# Swarm_Board_3.net
KiCad netlist of a schematic drawn in EAGLE
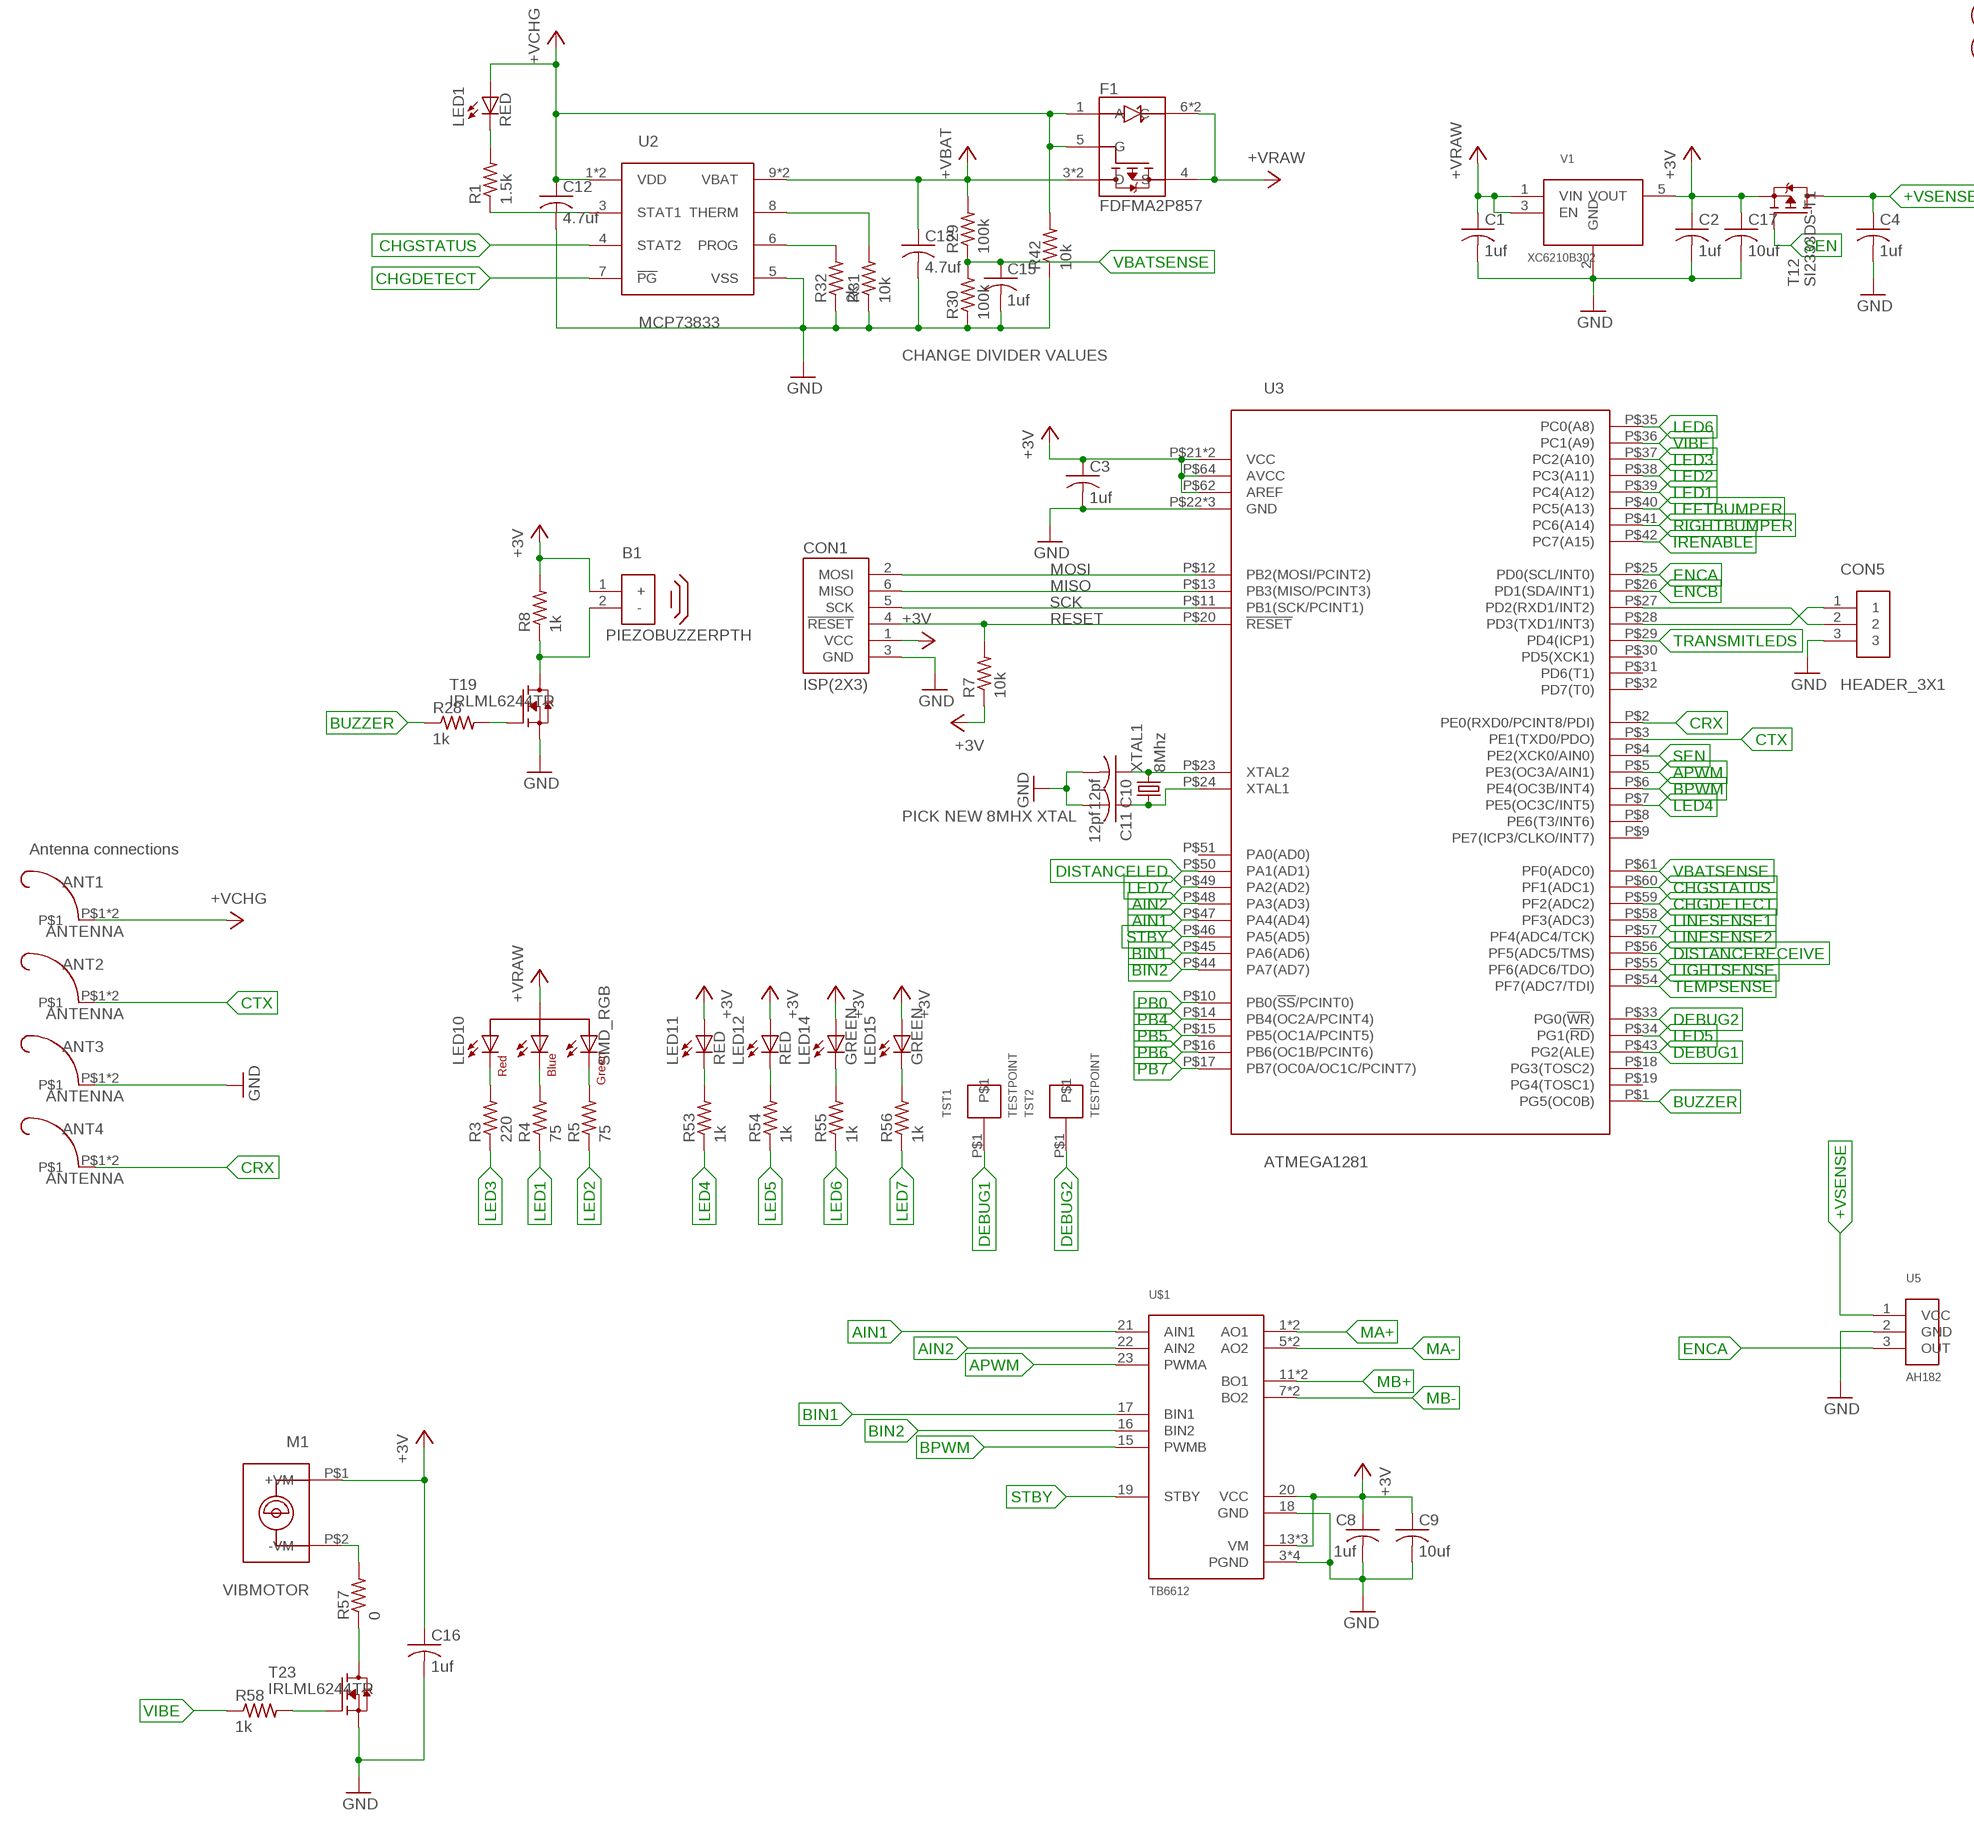
[diagram p0: schematic, sheet 1, part 1 of 2]
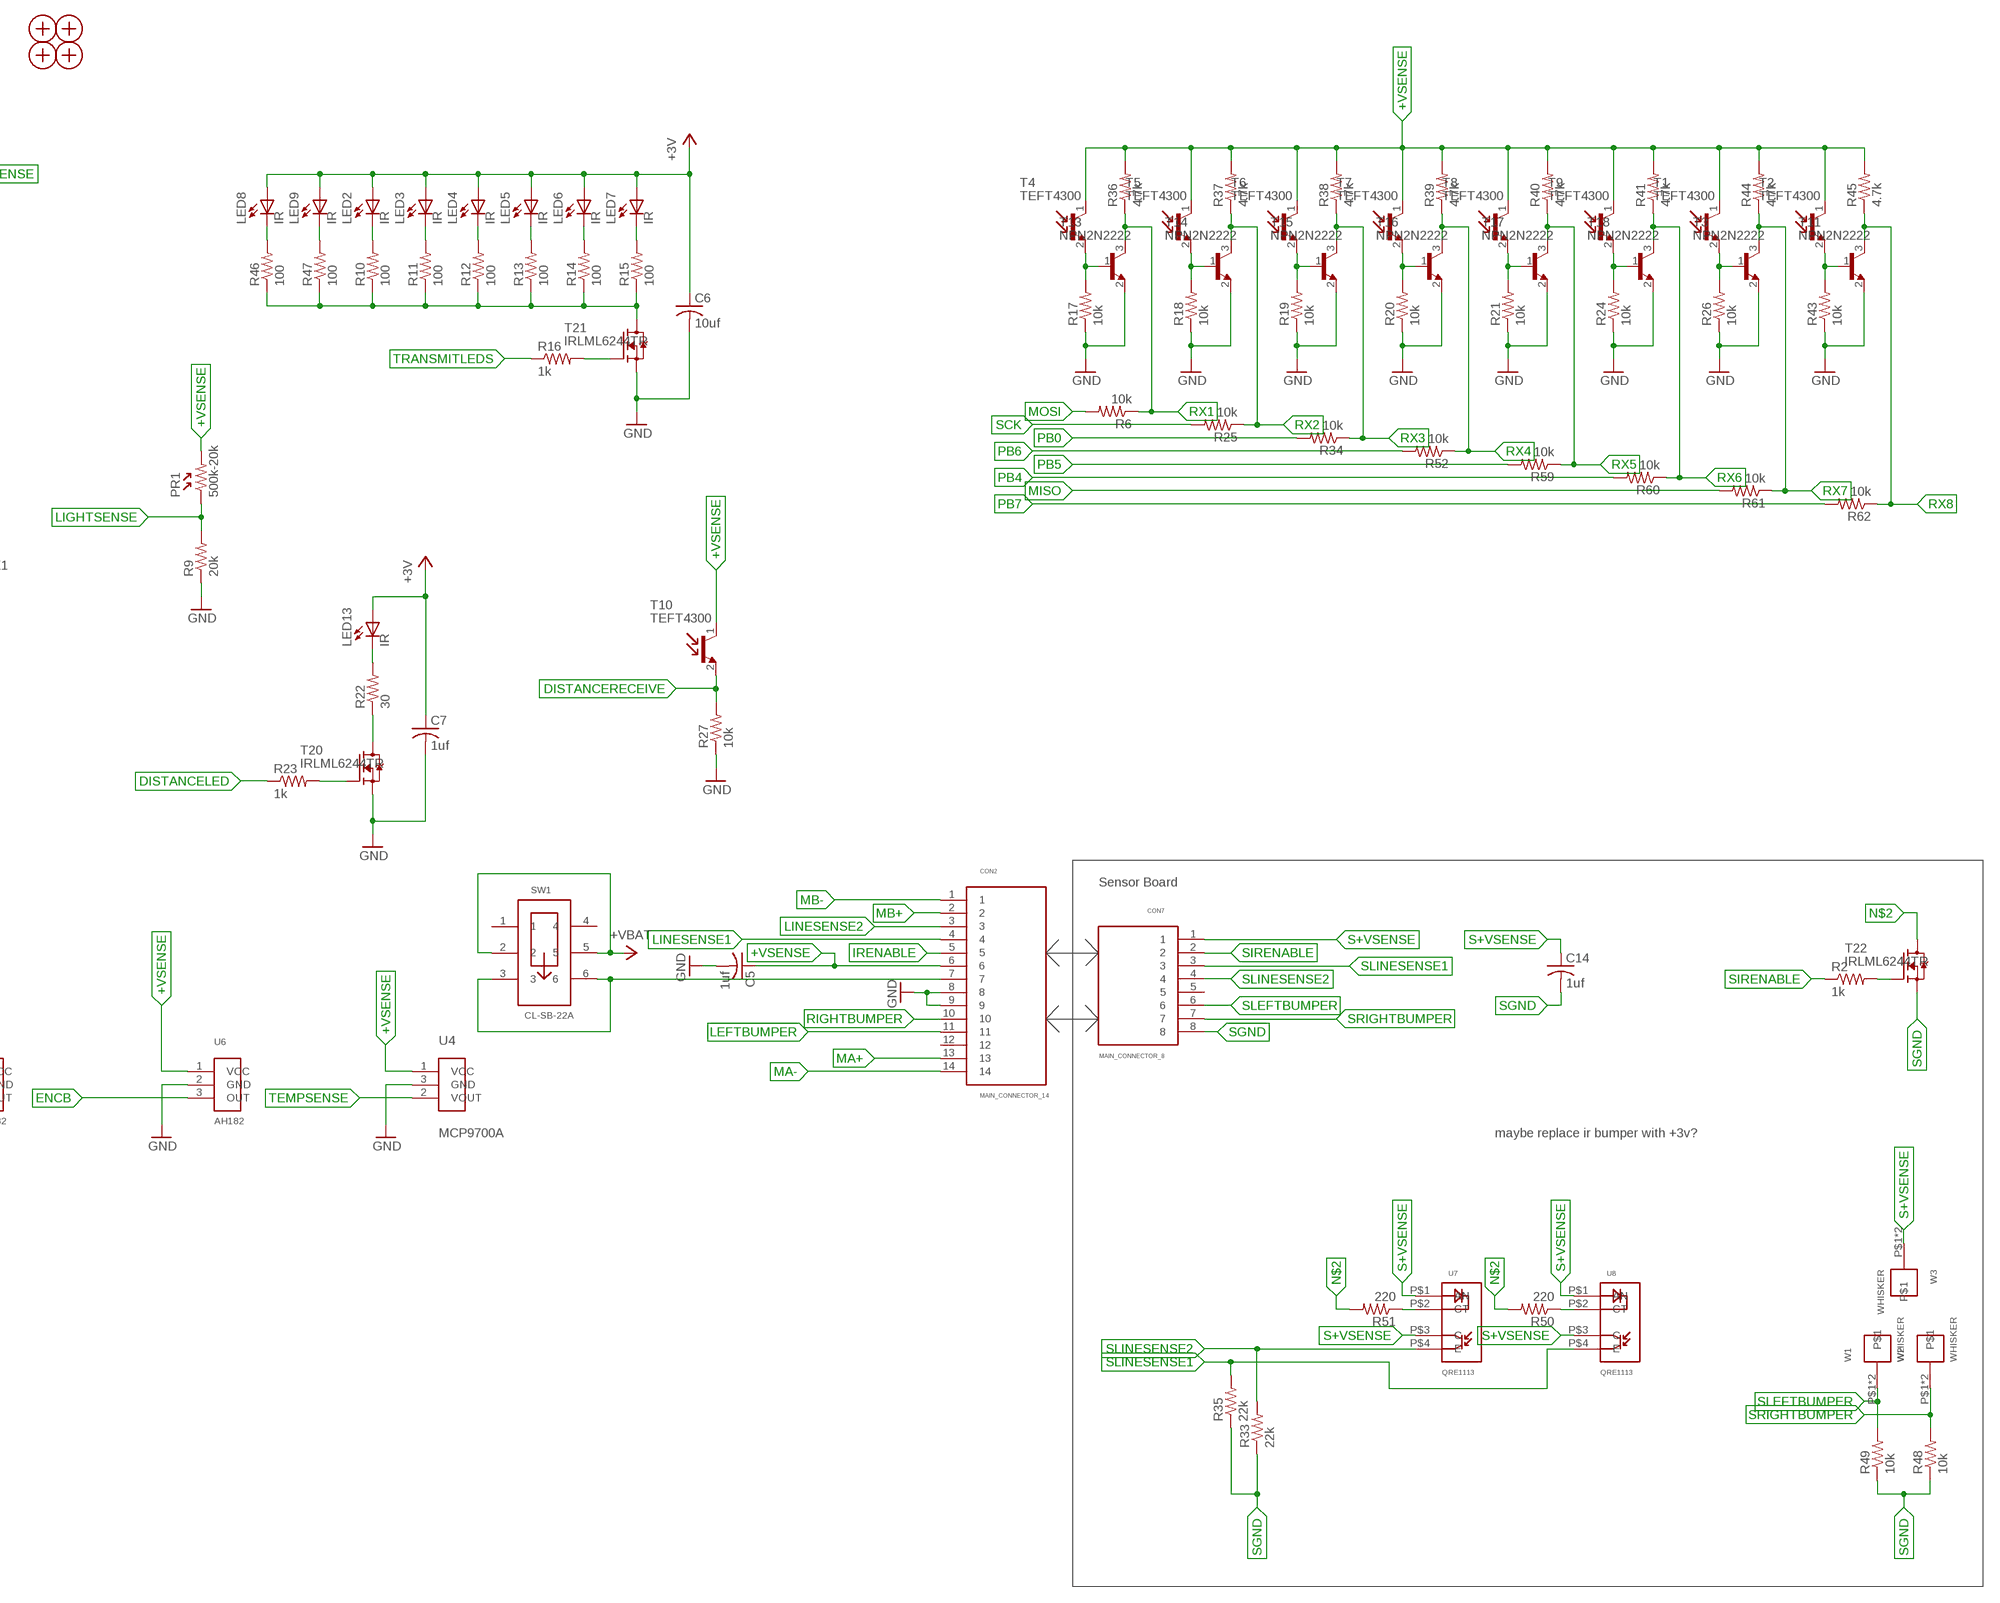
[diagram p1: schematic, sheet 1, part 2 of 2]

(export (version "E")
  (design (tool "Eeschema 10.0.6"))
  (components
    (comp (ref "ANT1")
      (value "ANTENNA")
      (footprint "eagle-import:ANTENNA")
      (libsource (lib "eagle-import") (part "ANTENNA"))
    )
    (comp (ref "ANT2")
      (value "ANTENNA")
      (footprint "eagle-import:ANTENNA")
      (libsource (lib "eagle-import") (part "ANTENNA"))
    )
    (comp (ref "ANT3")
      (value "ANTENNA")
      (footprint "eagle-import:ANTENNA")
      (libsource (lib "eagle-import") (part "ANTENNA"))
    )
    (comp (ref "ANT4")
      (value "ANTENNA")
      (footprint "eagle-import:ANTENNA")
      (libsource (lib "eagle-import") (part "ANTENNA"))
    )
    (comp (ref "B1")
      (value "PIEZOBUZZERPTH")
      (footprint "eagle-import:PIEZOBUZZER")
      (libsource (lib "eagle-import") (part "PIEZOBUZZERPTH"))
    )
    (comp (ref "C1")
      (value "1uf")
      (footprint "eagle-import:0603")
      (libsource (lib "eagle-import") (part "CAP0603"))
    )
    (comp (ref "C2")
      (value "1uf")
      (footprint "eagle-import:0603")
      (libsource (lib "eagle-import") (part "CAP0603"))
    )
    (comp (ref "C3")
      (value "1uf")
      (footprint "eagle-import:0603")
      (libsource (lib "eagle-import") (part "CAP0603"))
    )
    (comp (ref "C4")
      (value "1uf")
      (footprint "eagle-import:0603")
      (libsource (lib "eagle-import") (part "CAP0603"))
    )
    (comp (ref "C5")
      (value "1uf")
      (footprint "eagle-import:0603")
      (libsource (lib "eagle-import") (part "CAP0603"))
    )
    (comp (ref "C6")
      (value "10uf")
      (footprint "eagle-import:0805")
      (libsource (lib "eagle-import") (part "CAP0805"))
    )
    (comp (ref "C7")
      (value "1uf")
      (footprint "eagle-import:0603")
      (libsource (lib "eagle-import") (part "CAP0603"))
    )
    (comp (ref "C8")
      (value "1uf")
      (footprint "eagle-import:0603")
      (libsource (lib "eagle-import") (part "CAP0603"))
    )
    (comp (ref "C9")
      (value "10uf")
      (footprint "eagle-import:0805")
      (libsource (lib "eagle-import") (part "CAP0805"))
    )
    (comp (ref "C10")
      (value "12pf")
      (footprint "eagle-import:0603")
      (libsource (lib "eagle-import") (part "CAP0603"))
    )
    (comp (ref "C11")
      (value "12pf")
      (footprint "eagle-import:0603")
      (libsource (lib "eagle-import") (part "CAP0603"))
    )
    (comp (ref "C12")
      (value "4.7uf")
      (footprint "eagle-import:0603")
      (libsource (lib "eagle-import") (part "CAP0603"))
    )
    (comp (ref "C13")
      (value "4.7uf")
      (footprint "eagle-import:0603")
      (libsource (lib "eagle-import") (part "CAP0603"))
    )
    (comp (ref "C14")
      (value "1uf")
      (footprint "eagle-import:0603")
      (libsource (lib "eagle-import") (part "CAP0603"))
    )
    (comp (ref "C15")
      (value "1uf")
      (footprint "eagle-import:0603")
      (libsource (lib "eagle-import") (part "CAP0603"))
    )
    (comp (ref "C16")
      (value "1uf")
      (footprint "eagle-import:0603")
      (libsource (lib "eagle-import") (part "CAP0603"))
    )
    (comp (ref "C17")
      (value "10uf")
      (footprint "eagle-import:0805")
      (libsource (lib "eagle-import") (part "CAP0805"))
    )
    (comp (ref "CON1")
      (value "ISP(2X3)")
      (footprint "eagle-import:PINHEADER(2X3)")
      (libsource (lib "eagle-import") (part "ISP(2X3)"))
    )
    (comp (ref "CON2")
      (value "MAIN_CONNECTOR_14")
      (footprint "eagle-import:FEMALE_HEADER_2MM_2X7_SMD")
      (libsource (lib "eagle-import") (part "MAIN_CONNECTOR_14"))
    )
    (comp (ref "CON5")
      (value "HEADER_3X1")
      (footprint "eagle-import:3PINHEADER_.100_")
      (libsource (lib "eagle-import") (part "HEADER_3X1"))
    )
    (comp (ref "CON7")
      (value "MAIN_CONNECTOR_8")
      (footprint "eagle-import:FEMALE_HEADER_2MM_2X4")
      (libsource (lib "eagle-import") (part "MAIN_CONNECTOR_8"))
    )
    (comp (ref "F1")
      (value "FDFMA2P857")
      (footprint "eagle-import:MICROFET2X2MM")
      (libsource (lib "eagle-import") (part "FDFMA2P857"))
    )
    (comp (ref "H1")
      (value "MOUNTINGHOLE")
      (footprint "eagle-import:MOUNTINGHOLE")
      (libsource (lib "eagle-import") (part "MOUNTINGHOLE"))
    )
    (comp (ref "H2")
      (value "MOUNTINGHOLE")
      (footprint "eagle-import:MOUNTINGHOLE")
      (libsource (lib "eagle-import") (part "MOUNTINGHOLE"))
    )
    (comp (ref "H3")
      (value "MOUNTINGHOLE")
      (footprint "eagle-import:MOUNTINGHOLE")
      (libsource (lib "eagle-import") (part "MOUNTINGHOLE"))
    )
    (comp (ref "H4")
      (value "MOUNTINGHOLE")
      (footprint "eagle-import:MOUNTINGHOLE")
      (libsource (lib "eagle-import") (part "MOUNTINGHOLE"))
    )
    (comp (ref "LED1")
      (value "RED")
      (footprint "eagle-import:LED0603")
      (libsource (lib "eagle-import") (part "LED0603"))
    )
    (comp (ref "LED2")
      (value "IR")
      (footprint "eagle-import:5MM_LED_RA")
      (libsource (lib "eagle-import") (part "LED5MMRA"))
    )
    (comp (ref "LED3")
      (value "IR")
      (footprint "eagle-import:5MM_LED_RA")
      (libsource (lib "eagle-import") (part "LED5MMRA"))
    )
    (comp (ref "LED4")
      (value "IR")
      (footprint "eagle-import:5MM_LED_RA")
      (libsource (lib "eagle-import") (part "LED5MMRA"))
    )
    (comp (ref "LED5")
      (value "IR")
      (footprint "eagle-import:5MM_LED_RA")
      (libsource (lib "eagle-import") (part "LED5MMRA"))
    )
    (comp (ref "LED6")
      (value "IR")
      (footprint "eagle-import:5MM_LED_RA")
      (libsource (lib "eagle-import") (part "LED5MMRA"))
    )
    (comp (ref "LED7")
      (value "IR")
      (footprint "eagle-import:5MM_LED_RA")
      (libsource (lib "eagle-import") (part "LED5MMRA"))
    )
    (comp (ref "LED8")
      (value "IR")
      (footprint "eagle-import:5MM_LED_RA")
      (libsource (lib "eagle-import") (part "LED5MMRA"))
    )
    (comp (ref "LED9")
      (value "IR")
      (footprint "eagle-import:5MM_LED_RA")
      (libsource (lib "eagle-import") (part "LED5MMRA"))
    )
    (comp (ref "LED10")
      (value "SMD_RGB")
      (footprint "eagle-import:PLCC4")
      (libsource (lib "eagle-import") (part "SMD_RGB"))
    )
    (comp (ref "LED11")
      (value "RED")
      (footprint "eagle-import:LED0603")
      (libsource (lib "eagle-import") (part "LED0603"))
    )
    (comp (ref "LED12")
      (value "RED")
      (footprint "eagle-import:LED0603")
      (libsource (lib "eagle-import") (part "LED0603"))
    )
    (comp (ref "LED13")
      (value "IR")
      (footprint "eagle-import:5MM_LED_RA")
      (libsource (lib "eagle-import") (part "LED5MMRA"))
    )
    (comp (ref "LED14")
      (value "GREEN")
      (footprint "eagle-import:LED0603")
      (libsource (lib "eagle-import") (part "LED0603"))
    )
    (comp (ref "LED15")
      (value "GREEN")
      (footprint "eagle-import:LED0603")
      (libsource (lib "eagle-import") (part "LED0603"))
    )
    (comp (ref "M1")
      (value "VIBMOTOR")
      (footprint "eagle-import:VIBMOTOR")
      (libsource (lib "eagle-import") (part "VIBMOTOR"))
    )
    (comp (ref "PR1")
      (value "500k-20k")
      (footprint "eagle-import:CDSPHOTOCELL")
      (libsource (lib "eagle-import") (part "CDSPHOTORESISTOR"))
    )
    (comp (ref "R1")
      (value "1.5k")
      (footprint "eagle-import:0603")
      (libsource (lib "eagle-import") (part "RES0603"))
    )
    (comp (ref "R2")
      (value "1k")
      (footprint "eagle-import:0603")
      (libsource (lib "eagle-import") (part "RES0603"))
    )
    (comp (ref "R3")
      (value "220")
      (footprint "eagle-import:0603")
      (libsource (lib "eagle-import") (part "RES0603"))
    )
    (comp (ref "R4")
      (value "75")
      (footprint "eagle-import:0603")
      (libsource (lib "eagle-import") (part "RES0603"))
    )
    (comp (ref "R5")
      (value "75")
      (footprint "eagle-import:0603")
      (libsource (lib "eagle-import") (part "RES0603"))
    )
    (comp (ref "R6")
      (value "10k")
      (footprint "eagle-import:0603")
      (libsource (lib "eagle-import") (part "RES0603"))
    )
    (comp (ref "R7")
      (value "10k")
      (footprint "eagle-import:0603")
      (libsource (lib "eagle-import") (part "RES0603"))
    )
    (comp (ref "R8")
      (value "1k")
      (footprint "eagle-import:0603")
      (libsource (lib "eagle-import") (part "RES0603"))
    )
    (comp (ref "R9")
      (value "20k")
      (footprint "eagle-import:0603")
      (libsource (lib "eagle-import") (part "RES0603"))
    )
    (comp (ref "R10")
      (value "100")
      (footprint "eagle-import:0603")
      (libsource (lib "eagle-import") (part "RES0603"))
    )
    (comp (ref "R11")
      (value "100")
      (footprint "eagle-import:0603")
      (libsource (lib "eagle-import") (part "RES0603"))
    )
    (comp (ref "R12")
      (value "100")
      (footprint "eagle-import:0603")
      (libsource (lib "eagle-import") (part "RES0603"))
    )
    (comp (ref "R13")
      (value "100")
      (footprint "eagle-import:0603")
      (libsource (lib "eagle-import") (part "RES0603"))
    )
    (comp (ref "R14")
      (value "100")
      (footprint "eagle-import:0603")
      (libsource (lib "eagle-import") (part "RES0603"))
    )
    (comp (ref "R15")
      (value "100")
      (footprint "eagle-import:0603")
      (libsource (lib "eagle-import") (part "RES0603"))
    )
    (comp (ref "R16")
      (value "1k")
      (footprint "eagle-import:0603")
      (libsource (lib "eagle-import") (part "RES0603"))
    )
    (comp (ref "R17")
      (value "10k")
      (footprint "eagle-import:0603")
      (libsource (lib "eagle-import") (part "RES0603"))
    )
    (comp (ref "R18")
      (value "10k")
      (footprint "eagle-import:0603")
      (libsource (lib "eagle-import") (part "RES0603"))
    )
    (comp (ref "R19")
      (value "10k")
      (footprint "eagle-import:0603")
      (libsource (lib "eagle-import") (part "RES0603"))
    )
    (comp (ref "R20")
      (value "10k")
      (footprint "eagle-import:0603")
      (libsource (lib "eagle-import") (part "RES0603"))
    )
    (comp (ref "R21")
      (value "10k")
      (footprint "eagle-import:0603")
      (libsource (lib "eagle-import") (part "RES0603"))
    )
    (comp (ref "R22")
      (value "30")
      (footprint "eagle-import:0603")
      (libsource (lib "eagle-import") (part "RES0603"))
    )
    (comp (ref "R23")
      (value "1k")
      (footprint "eagle-import:0603")
      (libsource (lib "eagle-import") (part "RES0603"))
    )
    (comp (ref "R24")
      (value "10k")
      (footprint "eagle-import:0603")
      (libsource (lib "eagle-import") (part "RES0603"))
    )
    (comp (ref "R25")
      (value "10k")
      (footprint "eagle-import:0603")
      (libsource (lib "eagle-import") (part "RES0603"))
    )
    (comp (ref "R26")
      (value "10k")
      (footprint "eagle-import:0603")
      (libsource (lib "eagle-import") (part "RES0603"))
    )
    (comp (ref "R27")
      (value "10k")
      (footprint "eagle-import:0603")
      (libsource (lib "eagle-import") (part "RES0603"))
    )
    (comp (ref "R28")
      (value "1k")
      (footprint "eagle-import:0603")
      (libsource (lib "eagle-import") (part "RES0603"))
    )
    (comp (ref "R29")
      (value "100k")
      (footprint "eagle-import:0603")
      (libsource (lib "eagle-import") (part "RES0603"))
    )
    (comp (ref "R30")
      (value "100k")
      (footprint "eagle-import:0603")
      (libsource (lib "eagle-import") (part "RES0603"))
    )
    (comp (ref "R31")
      (value "10k")
      (footprint "eagle-import:0603")
      (libsource (lib "eagle-import") (part "RES0603"))
    )
    (comp (ref "R32")
      (value "2k")
      (footprint "eagle-import:0603")
      (libsource (lib "eagle-import") (part "RES0603"))
    )
    (comp (ref "R33")
      (value "22k")
      (footprint "eagle-import:0603")
      (libsource (lib "eagle-import") (part "RES0603"))
    )
    (comp (ref "R34")
      (value "10k")
      (footprint "eagle-import:0603")
      (libsource (lib "eagle-import") (part "RES0603"))
    )
    (comp (ref "R35")
      (value "22k")
      (footprint "eagle-import:0603")
      (libsource (lib "eagle-import") (part "RES0603"))
    )
    (comp (ref "R36")
      (value "4.7k")
      (footprint "eagle-import:0603")
      (libsource (lib "eagle-import") (part "RES0603"))
    )
    (comp (ref "R37")
      (value "4.7k")
      (footprint "eagle-import:0603")
      (libsource (lib "eagle-import") (part "RES0603"))
    )
    (comp (ref "R38")
      (value "4.7k")
      (footprint "eagle-import:0603")
      (libsource (lib "eagle-import") (part "RES0603"))
    )
    (comp (ref "R39")
      (value "4.7k")
      (footprint "eagle-import:0603")
      (libsource (lib "eagle-import") (part "RES0603"))
    )
    (comp (ref "R40")
      (value "4.7k")
      (footprint "eagle-import:0603")
      (libsource (lib "eagle-import") (part "RES0603"))
    )
    (comp (ref "R41")
      (value "4.7k")
      (footprint "eagle-import:0603")
      (libsource (lib "eagle-import") (part "RES0603"))
    )
    (comp (ref "R42")
      (value "10k")
      (footprint "eagle-import:0603")
      (libsource (lib "eagle-import") (part "RES0603"))
    )
    (comp (ref "R43")
      (value "10k")
      (footprint "eagle-import:0603")
      (libsource (lib "eagle-import") (part "RES0603"))
    )
    (comp (ref "R44")
      (value "4.7k")
      (footprint "eagle-import:0603")
      (libsource (lib "eagle-import") (part "RES0603"))
    )
    (comp (ref "R45")
      (value "4.7k")
      (footprint "eagle-import:0603")
      (libsource (lib "eagle-import") (part "RES0603"))
    )
    (comp (ref "R46")
      (value "100")
      (footprint "eagle-import:0603")
      (libsource (lib "eagle-import") (part "RES0603"))
    )
    (comp (ref "R47")
      (value "100")
      (footprint "eagle-import:0603")
      (libsource (lib "eagle-import") (part "RES0603"))
    )
    (comp (ref "R48")
      (value "10k")
      (footprint "eagle-import:0603")
      (libsource (lib "eagle-import") (part "RES0603"))
    )
    (comp (ref "R49")
      (value "10k")
      (footprint "eagle-import:0603")
      (libsource (lib "eagle-import") (part "RES0603"))
    )
    (comp (ref "R50")
      (value "220")
      (footprint "eagle-import:0603")
      (libsource (lib "eagle-import") (part "RES0603"))
    )
    (comp (ref "R51")
      (value "220")
      (footprint "eagle-import:0603")
      (libsource (lib "eagle-import") (part "RES0603"))
    )
    (comp (ref "R52")
      (value "10k")
      (footprint "eagle-import:0603")
      (libsource (lib "eagle-import") (part "RES0603"))
    )
    (comp (ref "R53")
      (value "1k")
      (footprint "eagle-import:0603")
      (libsource (lib "eagle-import") (part "RES0603"))
    )
    (comp (ref "R54")
      (value "1k")
      (footprint "eagle-import:0603")
      (libsource (lib "eagle-import") (part "RES0603"))
    )
    (comp (ref "R55")
      (value "1k")
      (footprint "eagle-import:0603")
      (libsource (lib "eagle-import") (part "RES0603"))
    )
    (comp (ref "R56")
      (value "1k")
      (footprint "eagle-import:0603")
      (libsource (lib "eagle-import") (part "RES0603"))
    )
    (comp (ref "R57")
      (value "0")
      (footprint "eagle-import:0603")
      (libsource (lib "eagle-import") (part "RES0603"))
    )
    (comp (ref "R58")
      (value "1k")
      (footprint "eagle-import:0603")
      (libsource (lib "eagle-import") (part "RES0603"))
    )
    (comp (ref "R59")
      (value "10k")
      (footprint "eagle-import:0603")
      (libsource (lib "eagle-import") (part "RES0603"))
    )
    (comp (ref "R60")
      (value "10k")
      (footprint "eagle-import:0603")
      (libsource (lib "eagle-import") (part "RES0603"))
    )
    (comp (ref "R61")
      (value "10k")
      (footprint "eagle-import:0603")
      (libsource (lib "eagle-import") (part "RES0603"))
    )
    (comp (ref "R62")
      (value "10k")
      (footprint "eagle-import:0603")
      (libsource (lib "eagle-import") (part "RES0603"))
    )
    (comp (ref "SW1")
      (value "CL-SB-22A")
      (footprint "eagle-import:CL-SB-22A-01T")
      (libsource (lib "eagle-import") (part "CL-SB-22A"))
    )
    (comp (ref "T1")
      (value "TEFT4300")
      (footprint "eagle-import:3MM_LED_RA")
      (libsource (lib "eagle-import") (part "TEFT4300"))
    )
    (comp (ref "T2")
      (value "TEFT4300")
      (footprint "eagle-import:3MM_LED_RA")
      (libsource (lib "eagle-import") (part "TEFT4300"))
    )
    (comp (ref "T3")
      (value "NPN2N2222")
      (footprint "eagle-import:SOT23")
      (libsource (lib "eagle-import") (part "NPN2N2222"))
    )
    (comp (ref "T4")
      (value "TEFT4300")
      (footprint "eagle-import:3MM_LED_RA")
      (libsource (lib "eagle-import") (part "TEFT4300"))
    )
    (comp (ref "T5")
      (value "TEFT4300")
      (footprint "eagle-import:3MM_LED_RA")
      (libsource (lib "eagle-import") (part "TEFT4300"))
    )
    (comp (ref "T6")
      (value "TEFT4300")
      (footprint "eagle-import:3MM_LED_RA")
      (libsource (lib "eagle-import") (part "TEFT4300"))
    )
    (comp (ref "T7")
      (value "TEFT4300")
      (footprint "eagle-import:3MM_LED_RA")
      (libsource (lib "eagle-import") (part "TEFT4300"))
    )
    (comp (ref "T8")
      (value "TEFT4300")
      (footprint "eagle-import:3MM_LED_RA")
      (libsource (lib "eagle-import") (part "TEFT4300"))
    )
    (comp (ref "T9")
      (value "TEFT4300")
      (footprint "eagle-import:3MM_LED_RA")
      (libsource (lib "eagle-import") (part "TEFT4300"))
    )
    (comp (ref "T10")
      (value "TEFT4300")
      (footprint "eagle-import:3MM_LED_RA")
      (libsource (lib "eagle-import") (part "TEFT4300"))
    )
    (comp (ref "T11")
      (value "NPN2N2222")
      (footprint "eagle-import:SOT23")
      (libsource (lib "eagle-import") (part "NPN2N2222"))
    )
    (comp (ref "T12")
      (value "SI2333DS-T1")
      (footprint "eagle-import:SOT23")
      (libsource (lib "eagle-import") (part "SI2333DS-T1"))
    )
    (comp (ref "T13")
      (value "NPN2N2222")
      (footprint "eagle-import:SOT23")
      (libsource (lib "eagle-import") (part "NPN2N2222"))
    )
    (comp (ref "T14")
      (value "NPN2N2222")
      (footprint "eagle-import:SOT23")
      (libsource (lib "eagle-import") (part "NPN2N2222"))
    )
    (comp (ref "T15")
      (value "NPN2N2222")
      (footprint "eagle-import:SOT23")
      (libsource (lib "eagle-import") (part "NPN2N2222"))
    )
    (comp (ref "T16")
      (value "NPN2N2222")
      (footprint "eagle-import:SOT23")
      (libsource (lib "eagle-import") (part "NPN2N2222"))
    )
    (comp (ref "T17")
      (value "NPN2N2222")
      (footprint "eagle-import:SOT23")
      (libsource (lib "eagle-import") (part "NPN2N2222"))
    )
    (comp (ref "T18")
      (value "NPN2N2222")
      (footprint "eagle-import:SOT23")
      (libsource (lib "eagle-import") (part "NPN2N2222"))
    )
    (comp (ref "T19")
      (value "IRLML6244TR")
      (footprint "eagle-import:SOT23")
      (libsource (lib "eagle-import") (part "IRLML6244TR"))
    )
    (comp (ref "T20")
      (value "IRLML6244TR")
      (footprint "eagle-import:SOT23")
      (libsource (lib "eagle-import") (part "IRLML6244TR"))
    )
    (comp (ref "T21")
      (value "IRLML6244TR")
      (footprint "eagle-import:SOT23")
      (libsource (lib "eagle-import") (part "IRLML6244TR"))
    )
    (comp (ref "T22")
      (value "IRLML6244TR")
      (footprint "eagle-import:SOT23")
      (libsource (lib "eagle-import") (part "IRLML6244TR"))
    )
    (comp (ref "T23")
      (value "IRLML6244TR")
      (footprint "eagle-import:SOT23")
      (libsource (lib "eagle-import") (part "IRLML6244TR"))
    )
    (comp (ref "TST1")
      (value "TESTPOINT")
      (footprint "eagle-import:TESTPOINT")
      (libsource (lib "eagle-import") (part "TESTPOINT"))
    )
    (comp (ref "TST2")
      (value "TESTPOINT")
      (footprint "eagle-import:TESTPOINT")
      (libsource (lib "eagle-import") (part "TESTPOINT"))
    )
    (comp (ref "U$1")
      (value "TB6612")
      (footprint "eagle-import:24SSOP")
      (libsource (lib "eagle-import") (part "TB6612"))
    )
    (comp (ref "U2")
      (value "MCP73833")
      (footprint "eagle-import:MSOP10")
      (libsource (lib "eagle-import") (part "MCP73833"))
    )
    (comp (ref "U3")
      (value "ATMEGA1281")
      (footprint "eagle-import:TQFP64")
      (libsource (lib "eagle-import") (part "ATMEGA1281"))
    )
    (comp (ref "U4")
      (value "MCP9700A")
      (footprint "eagle-import:SOT23")
      (libsource (lib "eagle-import") (part "MCP9700A"))
    )
    (comp (ref "U5")
      (value "AH182")
      (footprint "eagle-import:3PINHEADER_.100_")
      (libsource (lib "eagle-import") (part "AH182"))
    )
    (comp (ref "U6")
      (value "AH182")
      (footprint "eagle-import:3PINHEADER_.100_")
      (libsource (lib "eagle-import") (part "AH182"))
    )
    (comp (ref "U7")
      (value "QRE1113")
      (footprint "eagle-import:QRE1113")
      (libsource (lib "eagle-import") (part "QRE1113"))
    )
    (comp (ref "U8")
      (value "QRE1113")
      (footprint "eagle-import:QRE1113")
      (libsource (lib "eagle-import") (part "QRE1113"))
    )
    (comp (ref "V1")
      (value "XC6210B302")
      (footprint "eagle-import:(OT)SOT-23(5PAD)")
      (libsource (lib "eagle-import") (part "XC6210B302"))
    )
    (comp (ref "W1")
      (value "WHISKER")
      (footprint "eagle-import:WHISKER")
      (libsource (lib "eagle-import") (part "WHISKER"))
    )
    (comp (ref "W2")
      (value "WHISKER")
      (footprint "eagle-import:WHISKER")
      (libsource (lib "eagle-import") (part "WHISKER"))
    )
    (comp (ref "W3")
      (value "WHISKER")
      (footprint "eagle-import:WHISKER")
      (libsource (lib "eagle-import") (part "WHISKER"))
    )
    (comp (ref "XTAL1")
      (value "8Mhz")
      (footprint "eagle-import:SMDXTAL")
      (libsource (lib "eagle-import") (part "NX5032GA-10.000000MHZ"))
    )
  )
  (nets
    (net (code "1") (name "+3V") (class "Default")
      (node (ref "B1") (pin "1") (pinfunction "+_1") (pintype "bidirectional"))
      (node (ref "C16") (pin "1") (pinfunction "1_1") (pintype "passive"))
      (node (ref "C17") (pin "1") (pinfunction "1_1") (pintype "passive"))
      (node (ref "C2") (pin "1") (pinfunction "1_1") (pintype "passive"))
      (node (ref "C3") (pin "1") (pinfunction "1_1") (pintype "passive"))
      (node (ref "C6") (pin "1") (pinfunction "1_1") (pintype "passive"))
      (node (ref "C7") (pin "1") (pinfunction "1_1") (pintype "passive"))
      (node (ref "C8") (pin "1") (pinfunction "1_1") (pintype "passive"))
      (node (ref "C9") (pin "1") (pinfunction "1_1") (pintype "passive"))
      (node (ref "CON1") (pin "1") (pinfunction "VCC_1") (pintype "bidirectional"))
      (node (ref "LED11") (pin "2") (pinfunction "A_2") (pintype "passive"))
      (node (ref "LED12") (pin "2") (pinfunction "A_2") (pintype "passive"))
      (node (ref "LED13") (pin "1") (pinfunction "A_1") (pintype "passive"))
      (node (ref "LED14") (pin "2") (pinfunction "A_2") (pintype "passive"))
      (node (ref "LED15") (pin "2") (pinfunction "A_2") (pintype "passive"))
      (node (ref "LED2") (pin "1") (pinfunction "A_1") (pintype "passive"))
      (node (ref "LED3") (pin "1") (pinfunction "A_1") (pintype "passive"))
      (node (ref "LED4") (pin "1") (pinfunction "A_1") (pintype "passive"))
      (node (ref "LED5") (pin "1") (pinfunction "A_1") (pintype "passive"))
      (node (ref "LED6") (pin "1") (pinfunction "A_1") (pintype "passive"))
      (node (ref "LED7") (pin "1") (pinfunction "A_1") (pintype "passive"))
      (node (ref "LED8") (pin "1") (pinfunction "A_1") (pintype "passive"))
      (node (ref "LED9") (pin "1") (pinfunction "A_1") (pintype "passive"))
      (node (ref "M1") (pin "P$1") (pinfunction "+VM_P$1") (pintype "bidirectional"))
      (node (ref "R7") (pin "1") (pinfunction "1_1") (pintype "passive"))
      (node (ref "R8") (pin "2") (pinfunction "2_2") (pintype "passive"))
      (node (ref "T12") (pin "2") (pinfunction "S_2") (pintype "passive"))
      (node (ref "U$1") (pin "13") (pinfunction "VM_13") (pintype "bidirectional"))
      (node (ref "U$1") (pin "14") (pinfunction "VM_14") (pintype "bidirectional"))
      (node (ref "U$1") (pin "20") (pinfunction "VCC_20") (pintype "bidirectional"))
      (node (ref "U$1") (pin "24") (pinfunction "VM_24") (pintype "bidirectional"))
      (node (ref "U3") (pin "P$21") (pinfunction "VCC_P$21") (pintype "bidirectional"))
      (node (ref "U3") (pin "P$52") (pinfunction "VCC_P$52") (pintype "bidirectional"))
      (node (ref "U3") (pin "P$62") (pinfunction "AREF_P$62") (pintype "bidirectional"))
      (node (ref "U3") (pin "P$64") (pinfunction "AVCC_P$64") (pintype "bidirectional"))
      (node (ref "V1") (pin "5") (pinfunction "VOUT_5") (pintype "bidirectional"))
    )
    (net (code "2") (name "+VBAT") (class "Default")
      (node (ref "C13") (pin "1") (pinfunction "1_1") (pintype "passive"))
      (node (ref "F1") (pin "3") (pinfunction "D_3") (pintype "bidirectional"))
      (node (ref "F1") (pin "8") (pinfunction "D_8") (pintype "bidirectional"))
      (node (ref "R29") (pin "2") (pinfunction "2_2") (pintype "passive"))
      (node (ref "SW1") (pin "2") (pinfunction "2_2") (pintype "bidirectional"))
      (node (ref "SW1") (pin "5") (pinfunction "5_5") (pintype "bidirectional"))
      (node (ref "U2") (pin "10") (pinfunction "VBAT_10") (pintype "bidirectional"))
      (node (ref "U2") (pin "9") (pinfunction "VBAT_9") (pintype "bidirectional"))
    )
    (net (code "3") (name "+VCHG") (class "Default")
      (node (ref "ANT1") (pin "P$1") (pinfunction "P$1_P$1") (pintype "bidirectional"))
      (node (ref "ANT1") (pin "P$2") (pinfunction "P$1_P$2") (pintype "bidirectional"))
      (node (ref "C12") (pin "1") (pinfunction "1_1") (pintype "passive"))
      (node (ref "F1") (pin "1") (pinfunction "A_1") (pintype "bidirectional"))
      (node (ref "F1") (pin "5") (pinfunction "G_5") (pintype "bidirectional"))
      (node (ref "LED1") (pin "2") (pinfunction "A_2") (pintype "passive"))
      (node (ref "R42") (pin "2") (pinfunction "2_2") (pintype "passive"))
      (node (ref "U2") (pin "1") (pinfunction "VDD_1") (pintype "bidirectional"))
      (node (ref "U2") (pin "2") (pinfunction "VDD_2") (pintype "bidirectional"))
    )
    (net (code "4") (name "+VRAW") (class "Default")
      (node (ref "C1") (pin "1") (pinfunction "1_1") (pintype "passive"))
      (node (ref "F1") (pin "4") (pinfunction "S_4") (pintype "bidirectional"))
      (node (ref "F1") (pin "6") (pinfunction "C_6") (pintype "bidirectional"))
      (node (ref "F1") (pin "7") (pinfunction "C_7") (pintype "bidirectional"))
      (node (ref "LED10") (pin "2") (pinfunction "COMMONANODE_2") (pintype "passive"))
      (node (ref "V1") (pin "1") (pinfunction "VIN_1") (pintype "bidirectional"))
      (node (ref "V1") (pin "3") (pinfunction "EN_3") (pintype "bidirectional"))
    )
    (net (code "5") (name "+VSENSE") (class "Default")
      (node (ref "C4") (pin "1") (pinfunction "1_1") (pintype "passive"))
      (node (ref "C5") (pin "1") (pinfunction "1_1") (pintype "passive"))
      (node (ref "CON2") (pin "6") (pinfunction "6_6") (pintype "bidirectional"))
      (node (ref "PR1") (pin "2") (pinfunction "2_2") (pintype "passive"))
      (node (ref "R36") (pin "2") (pinfunction "2_2") (pintype "passive"))
      (node (ref "R37") (pin "2") (pinfunction "2_2") (pintype "passive"))
      (node (ref "R38") (pin "2") (pinfunction "2_2") (pintype "passive"))
      (node (ref "R39") (pin "2") (pinfunction "2_2") (pintype "passive"))
      (node (ref "R40") (pin "2") (pinfunction "2_2") (pintype "passive"))
      (node (ref "R41") (pin "2") (pinfunction "2_2") (pintype "passive"))
      (node (ref "R44") (pin "2") (pinfunction "2_2") (pintype "passive"))
      (node (ref "R45") (pin "2") (pinfunction "2_2") (pintype "passive"))
      (node (ref "T1") (pin "1") (pinfunction "C_1") (pintype "passive"))
      (node (ref "T10") (pin "1") (pinfunction "C_1") (pintype "passive"))
      (node (ref "T12") (pin "3") (pinfunction "D_3") (pintype "passive"))
      (node (ref "T2") (pin "1") (pinfunction "C_1") (pintype "passive"))
      (node (ref "T4") (pin "1") (pinfunction "C_1") (pintype "passive"))
      (node (ref "T5") (pin "1") (pinfunction "C_1") (pintype "passive"))
      (node (ref "T6") (pin "1") (pinfunction "C_1") (pintype "passive"))
      (node (ref "T7") (pin "1") (pinfunction "C_1") (pintype "passive"))
      (node (ref "T8") (pin "1") (pinfunction "C_1") (pintype "passive"))
      (node (ref "T9") (pin "1") (pinfunction "C_1") (pintype "passive"))
      (node (ref "U4") (pin "1") (pinfunction "VCC_1") (pintype "bidirectional"))
      (node (ref "U5") (pin "1") (pinfunction "VCC_1") (pintype "bidirectional"))
      (node (ref "U6") (pin "1") (pinfunction "VCC_1") (pintype "bidirectional"))
    )
    (net (code "6") (name "/RESET") (class "Default")
      (node (ref "CON1") (pin "4") (pinfunction "~{RESET}_4") (pintype "bidirectional"))
      (node (ref "R7") (pin "2") (pinfunction "2_2") (pintype "passive"))
      (node (ref "U3") (pin "P$20") (pinfunction "~{RESET}_P$20") (pintype "bidirectional"))
    )
    (net (code "7") (name "AIN1") (class "Default")
      (node (ref "U$1") (pin "21") (pinfunction "AIN1_21") (pintype "bidirectional"))
      (node (ref "U3") (pin "P$47") (pinfunction "PA4(AD4)_P$47") (pintype "bidirectional"))
    )
    (net (code "8") (name "AIN2") (class "Default")
      (node (ref "U$1") (pin "22") (pinfunction "AIN2_22") (pintype "bidirectional"))
      (node (ref "U3") (pin "P$48") (pinfunction "PA3(AD3)_P$48") (pintype "bidirectional"))
    )
    (net (code "9") (name "APWM") (class "Default")
      (node (ref "U$1") (pin "23") (pinfunction "PWMA_23") (pintype "bidirectional"))
      (node (ref "U3") (pin "P$5") (pinfunction "PE3(OC3A/AIN1)_P$5") (pintype "bidirectional"))
    )
    (net (code "10") (name "BIN1") (class "Default")
      (node (ref "U$1") (pin "17") (pinfunction "BIN1_17") (pintype "bidirectional"))
      (node (ref "U3") (pin "P$45") (pinfunction "PA6(AD6)_P$45") (pintype "bidirectional"))
    )
    (net (code "11") (name "BIN2") (class "Default")
      (node (ref "U$1") (pin "16") (pinfunction "BIN2_16") (pintype "bidirectional"))
      (node (ref "U3") (pin "P$44") (pinfunction "PA7(AD7)_P$44") (pintype "bidirectional"))
    )
    (net (code "12") (name "BPWM") (class "Default")
      (node (ref "U$1") (pin "15") (pinfunction "PWMB_15") (pintype "bidirectional"))
      (node (ref "U3") (pin "P$6") (pinfunction "PE4(OC3B/INT4)_P$6") (pintype "bidirectional"))
    )
    (net (code "13") (name "BUZZER") (class "Default")
      (node (ref "R28") (pin "1") (pinfunction "1_1") (pintype "passive"))
      (node (ref "U3") (pin "P$1") (pinfunction "PG5(OC0B)_P$1") (pintype "bidirectional"))
    )
    (net (code "14") (name "CHGDETECT") (class "Default")
      (node (ref "U2") (pin "7") (pinfunction "~{PG}_7") (pintype "bidirectional"))
      (node (ref "U3") (pin "P$59") (pinfunction "PF2(ADC2)_P$59") (pintype "bidirectional"))
    )
    (net (code "15") (name "CHGSTATUS") (class "Default")
      (node (ref "U2") (pin "4") (pinfunction "STAT2_4") (pintype "bidirectional"))
      (node (ref "U3") (pin "P$60") (pinfunction "PF1(ADC1)_P$60") (pintype "bidirectional"))
    )
    (net (code "16") (name "CRX") (class "Default")
      (node (ref "ANT4") (pin "P$1") (pinfunction "P$1_P$1") (pintype "bidirectional"))
      (node (ref "ANT4") (pin "P$2") (pinfunction "P$1_P$2") (pintype "bidirectional"))
      (node (ref "U3") (pin "P$2") (pinfunction "PE0(RXD0/PCINT8/PDI)_P$2") (pintype "bidirectional"))
    )
    (net (code "17") (name "CTX") (class "Default")
      (node (ref "ANT2") (pin "P$1") (pinfunction "P$1_P$1") (pintype "bidirectional"))
      (node (ref "ANT2") (pin "P$2") (pinfunction "P$1_P$2") (pintype "bidirectional"))
      (node (ref "U3") (pin "P$3") (pinfunction "PE1(TXD0/PDO)_P$3") (pintype "bidirectional"))
    )
    (net (code "18") (name "DEBUG1") (class "Default")
      (node (ref "TST1") (pin "P$1") (pinfunction "P$1_P$1") (pintype "bidirectional"))
      (node (ref "U3") (pin "P$43") (pinfunction "PG2(ALE)_P$43") (pintype "bidirectional"))
    )
    (net (code "19") (name "DEBUG2") (class "Default")
      (node (ref "TST2") (pin "P$1") (pinfunction "P$1_P$1") (pintype "bidirectional"))
      (node (ref "U3") (pin "P$33") (pinfunction "PG0(~{WR})_P$33") (pintype "bidirectional"))
    )
    (net (code "20") (name "DISTANCELED") (class "Default")
      (node (ref "R23") (pin "1") (pinfunction "1_1") (pintype "passive"))
      (node (ref "U3") (pin "P$50") (pinfunction "PA1(AD1)_P$50") (pintype "bidirectional"))
    )
    (net (code "21") (name "DISTANCERECEIVE") (class "Default")
      (node (ref "R27") (pin "2") (pinfunction "2_2") (pintype "passive"))
      (node (ref "T10") (pin "2") (pinfunction "E_2") (pintype "passive"))
      (node (ref "U3") (pin "P$56") (pinfunction "PF5(ADC5/TMS)_P$56") (pintype "bidirectional"))
    )
    (net (code "22") (name "ENCA") (class "Default")
      (node (ref "U3") (pin "P$25") (pinfunction "PD0(SCL/INT0)_P$25") (pintype "bidirectional"))
      (node (ref "U5") (pin "3") (pinfunction "OUT_3") (pintype "bidirectional"))
    )
    (net (code "23") (name "ENCB") (class "Default")
      (node (ref "U3") (pin "P$26") (pinfunction "PD1(SDA/INT1)_P$26") (pintype "bidirectional"))
      (node (ref "U6") (pin "3") (pinfunction "OUT_3") (pintype "bidirectional"))
    )
    (net (code "24") (name "GND") (class "Default")
      (node (ref "ANT3") (pin "P$1") (pinfunction "P$1_P$1") (pintype "bidirectional"))
      (node (ref "ANT3") (pin "P$2") (pinfunction "P$1_P$2") (pintype "bidirectional"))
      (node (ref "C1") (pin "2") (pinfunction "2_2") (pintype "passive"))
      (node (ref "C10") (pin "2") (pinfunction "2_2") (pintype "passive"))
      (node (ref "C11") (pin "2") (pinfunction "2_2") (pintype "passive"))
      (node (ref "C12") (pin "2") (pinfunction "2_2") (pintype "passive"))
      (node (ref "C13") (pin "2") (pinfunction "2_2") (pintype "passive"))
      (node (ref "C15") (pin "2") (pinfunction "2_2") (pintype "passive"))
      (node (ref "C16") (pin "2") (pinfunction "2_2") (pintype "passive"))
      (node (ref "C17") (pin "2") (pinfunction "2_2") (pintype "passive"))
      (node (ref "C2") (pin "2") (pinfunction "2_2") (pintype "passive"))
      (node (ref "C3") (pin "2") (pinfunction "2_2") (pintype "passive"))
      (node (ref "C4") (pin "2") (pinfunction "2_2") (pintype "passive"))
      (node (ref "C5") (pin "2") (pinfunction "2_2") (pintype "passive"))
      (node (ref "C6") (pin "2") (pinfunction "2_2") (pintype "passive"))
      (node (ref "C7") (pin "2") (pinfunction "2_2") (pintype "passive"))
      (node (ref "C8") (pin "2") (pinfunction "2_2") (pintype "passive"))
      (node (ref "C9") (pin "2") (pinfunction "2_2") (pintype "passive"))
      (node (ref "CON1") (pin "3") (pinfunction "GND_3") (pintype "bidirectional"))
      (node (ref "CON2") (pin "8") (pinfunction "8_8") (pintype "bidirectional"))
      (node (ref "CON2") (pin "9") (pinfunction "9_9") (pintype "bidirectional"))
      (node (ref "CON5") (pin "3") (pinfunction "3_3") (pintype "bidirectional"))
      (node (ref "R17") (pin "1") (pinfunction "1_1") (pintype "passive"))
      (node (ref "R18") (pin "1") (pinfunction "1_1") (pintype "passive"))
      (node (ref "R19") (pin "1") (pinfunction "1_1") (pintype "passive"))
      (node (ref "R20") (pin "1") (pinfunction "1_1") (pintype "passive"))
      (node (ref "R21") (pin "1") (pinfunction "1_1") (pintype "passive"))
      (node (ref "R24") (pin "1") (pinfunction "1_1") (pintype "passive"))
      (node (ref "R26") (pin "1") (pinfunction "1_1") (pintype "passive"))
      (node (ref "R27") (pin "1") (pinfunction "1_1") (pintype "passive"))
      (node (ref "R30") (pin "1") (pinfunction "1_1") (pintype "passive"))
      (node (ref "R31") (pin "1") (pinfunction "1_1") (pintype "passive"))
      (node (ref "R32") (pin "1") (pinfunction "1_1") (pintype "passive"))
      (node (ref "R42") (pin "1") (pinfunction "1_1") (pintype "passive"))
      (node (ref "R43") (pin "1") (pinfunction "1_1") (pintype "passive"))
      (node (ref "R9") (pin "1") (pinfunction "1_1") (pintype "passive"))
      (node (ref "T11") (pin "2") (pinfunction "E_2") (pintype "passive"))
      (node (ref "T13") (pin "2") (pinfunction "E_2") (pintype "passive"))
      (node (ref "T14") (pin "2") (pinfunction "E_2") (pintype "passive"))
      (node (ref "T15") (pin "2") (pinfunction "E_2") (pintype "passive"))
      (node (ref "T16") (pin "2") (pinfunction "E_2") (pintype "passive"))
      (node (ref "T17") (pin "2") (pinfunction "E_2") (pintype "passive"))
      (node (ref "T18") (pin "2") (pinfunction "E_2") (pintype "passive"))
      (node (ref "T19") (pin "2") (pinfunction "S_2") (pintype "passive"))
      (node (ref "T20") (pin "2") (pinfunction "S_2") (pintype "passive"))
      (node (ref "T21") (pin "2") (pinfunction "S_2") (pintype "passive"))
      (node (ref "T23") (pin "2") (pinfunction "S_2") (pintype "passive"))
      (node (ref "T3") (pin "2") (pinfunction "E_2") (pintype "passive"))
      (node (ref "U$1") (pin "10") (pinfunction "PGND_10") (pintype "bidirectional"))
      (node (ref "U$1") (pin "18") (pinfunction "GND_18") (pintype "bidirectional"))
      (node (ref "U$1") (pin "3") (pinfunction "PGND_3") (pintype "bidirectional"))
      (node (ref "U$1") (pin "4") (pinfunction "PGND_4") (pintype "bidirectional"))
      (node (ref "U$1") (pin "9") (pinfunction "PGND_9") (pintype "bidirectional"))
      (node (ref "U2") (pin "5") (pinfunction "VSS_5") (pintype "bidirectional"))
      (node (ref "U3") (pin "P$22") (pinfunction "GND_P$22") (pintype "bidirectional"))
      (node (ref "U3") (pin "P$53") (pinfunction "GND_P$53") (pintype "bidirectional"))
      (node (ref "U3") (pin "P$63") (pinfunction "GND_P$63") (pintype "bidirectional"))
      (node (ref "U4") (pin "3") (pinfunction "GND_3") (pintype "bidirectional"))
      (node (ref "U5") (pin "2") (pinfunction "GND_2") (pintype "bidirectional"))
      (node (ref "U6") (pin "2") (pinfunction "GND_2") (pintype "bidirectional"))
      (node (ref "V1") (pin "2") (pinfunction "GND_2") (pintype "bidirectional"))
    )
    (net (code "25") (name "IRENABLE") (class "Default")
      (node (ref "CON2") (pin "5") (pinfunction "5_5") (pintype "bidirectional"))
      (node (ref "U3") (pin "P$42") (pinfunction "PC7(A15)_P$42") (pintype "bidirectional"))
    )
    (net (code "26") (name "LED1") (class "Default")
      (node (ref "R4") (pin "1") (pinfunction "1_1") (pintype "passive"))
      (node (ref "U3") (pin "P$39") (pinfunction "PC4(A12)_P$39") (pintype "bidirectional"))
    )
    (net (code "27") (name "LED2") (class "Default")
      (node (ref "R5") (pin "1") (pinfunction "1_1") (pintype "passive"))
      (node (ref "U3") (pin "P$38") (pinfunction "PC3(A11)_P$38") (pintype "bidirectional"))
    )
    (net (code "28") (name "LED3") (class "Default")
      (node (ref "R3") (pin "1") (pinfunction "1_1") (pintype "passive"))
      (node (ref "U3") (pin "P$37") (pinfunction "PC2(A10)_P$37") (pintype "bidirectional"))
    )
    (net (code "29") (name "LED4") (class "Default")
      (node (ref "R53") (pin "1") (pinfunction "1_1") (pintype "passive"))
      (node (ref "U3") (pin "P$7") (pinfunction "PE5(OC3C/INT5)_P$7") (pintype "bidirectional"))
    )
    (net (code "30") (name "LED5") (class "Default")
      (node (ref "R54") (pin "1") (pinfunction "1_1") (pintype "passive"))
      (node (ref "U3") (pin "P$34") (pinfunction "PG1(~{RD})_P$34") (pintype "bidirectional"))
    )
    (net (code "31") (name "LED6") (class "Default")
      (node (ref "R55") (pin "1") (pinfunction "1_1") (pintype "passive"))
      (node (ref "U3") (pin "P$35") (pinfunction "PC0(A8)_P$35") (pintype "bidirectional"))
    )
    (net (code "32") (name "LED7") (class "Default")
      (node (ref "R56") (pin "1") (pinfunction "1_1") (pintype "passive"))
      (node (ref "U3") (pin "P$49") (pinfunction "PA2(AD2)_P$49") (pintype "bidirectional"))
    )
    (net (code "33") (name "LEFTBUMPER") (class "Default")
      (node (ref "CON2") (pin "11") (pinfunction "11_11") (pintype "bidirectional"))
      (node (ref "U3") (pin "P$40") (pinfunction "PC5(A13)_P$40") (pintype "bidirectional"))
    )
    (net (code "34") (name "LIGHTSENSE") (class "Default")
      (node (ref "PR1") (pin "1") (pinfunction "1_1") (pintype "passive"))
      (node (ref "R9") (pin "2") (pinfunction "2_2") (pintype "passive"))
      (node (ref "U3") (pin "P$55") (pinfunction "PF6(ADC6/TDO)_P$55") (pintype "bidirectional"))
    )
    (net (code "35") (name "LINESENSE1") (class "Default")
      (node (ref "CON2") (pin "4") (pinfunction "4_4") (pintype "bidirectional"))
      (node (ref "U3") (pin "P$58") (pinfunction "PF3(ADC3)_P$58") (pintype "bidirectional"))
    )
    (net (code "36") (name "LINESENSE2") (class "Default")
      (node (ref "CON2") (pin "3") (pinfunction "3_3") (pintype "bidirectional"))
      (node (ref "U3") (pin "P$57") (pinfunction "PF4(ADC4/TCK)_P$57") (pintype "bidirectional"))
    )
    (net (code "37") (name "MA+") (class "Default")
      (node (ref "CON2") (pin "13") (pinfunction "13_13") (pintype "bidirectional"))
      (node (ref "U$1") (pin "1") (pinfunction "AO1_1") (pintype "bidirectional"))
      (node (ref "U$1") (pin "2") (pinfunction "AO1_2") (pintype "bidirectional"))
    )
    (net (code "38") (name "MA-") (class "Default")
      (node (ref "CON2") (pin "14") (pinfunction "14_14") (pintype "bidirectional"))
      (node (ref "U$1") (pin "5") (pinfunction "AO2_5") (pintype "bidirectional"))
      (node (ref "U$1") (pin "6") (pinfunction "AO2_6") (pintype "bidirectional"))
    )
    (net (code "39") (name "MB+") (class "Default")
      (node (ref "CON2") (pin "2") (pinfunction "2_2") (pintype "bidirectional"))
      (node (ref "U$1") (pin "11") (pinfunction "BO1_11") (pintype "bidirectional"))
      (node (ref "U$1") (pin "12") (pinfunction "BO1_12") (pintype "bidirectional"))
    )
    (net (code "40") (name "MB-") (class "Default")
      (node (ref "CON2") (pin "1") (pinfunction "1_1") (pintype "bidirectional"))
      (node (ref "U$1") (pin "7") (pinfunction "BO2_7") (pintype "bidirectional"))
      (node (ref "U$1") (pin "8") (pinfunction "BO2_8") (pintype "bidirectional"))
    )
    (net (code "41") (name "MISO") (class "Default")
      (node (ref "CON1") (pin "6") (pinfunction "MISO_6") (pintype "bidirectional"))
      (node (ref "R61") (pin "2") (pinfunction "2_2") (pintype "passive"))
      (node (ref "U3") (pin "P$13") (pinfunction "PB3(MISO/PCINT3)_P$13") (pintype "bidirectional"))
    )
    (net (code "42") (name "MOSI") (class "Default")
      (node (ref "CON1") (pin "2") (pinfunction "MOSI_2") (pintype "bidirectional"))
      (node (ref "R6") (pin "2") (pinfunction "2_2") (pintype "passive"))
      (node (ref "U3") (pin "P$12") (pinfunction "PB2(MOSI/PCINT2)_P$12") (pintype "bidirectional"))
    )
    (net (code "43") (name "N$2") (class "Default")
      (node (ref "R50") (pin "2") (pinfunction "2_2") (pintype "passive"))
      (node (ref "R51") (pin "2") (pinfunction "2_2") (pintype "passive"))
      (node (ref "T22") (pin "3") (pinfunction "D_3") (pintype "passive"))
    )
    (net (code "44") (name "Net-(B1--)") (class "Default")
      (node (ref "B1") (pin "2") (pinfunction "-_2") (pintype "bidirectional"))
      (node (ref "R8") (pin "1") (pinfunction "1_1") (pintype "passive"))
      (node (ref "T19") (pin "3") (pinfunction "D_3") (pintype "passive"))
    )
    (net (code "45") (name "Net-(CON2-Pad7)") (class "Default")
      (node (ref "CON2") (pin "7") (pinfunction "7_7") (pintype "bidirectional"))
      (node (ref "SW1") (pin "3") (pinfunction "3_3") (pintype "bidirectional"))
      (node (ref "SW1") (pin "6") (pinfunction "6_6") (pintype "bidirectional"))
    )
    (net (code "46") (name "Net-(LED1-C)") (class "Default")
      (node (ref "LED1") (pin "1") (pinfunction "C_1") (pintype "passive"))
      (node (ref "R1") (pin "2") (pinfunction "2_2") (pintype "passive"))
    )
    (net (code "47") (name "Net-(LED2-C)") (class "Default")
      (node (ref "LED2") (pin "2") (pinfunction "C_2") (pintype "passive"))
      (node (ref "R10") (pin "2") (pinfunction "2_2") (pintype "passive"))
    )
    (net (code "48") (name "Net-(LED3-C)") (class "Default")
      (node (ref "LED3") (pin "2") (pinfunction "C_2") (pintype "passive"))
      (node (ref "R11") (pin "2") (pinfunction "2_2") (pintype "passive"))
    )
    (net (code "49") (name "Net-(LED4-C)") (class "Default")
      (node (ref "LED4") (pin "2") (pinfunction "C_2") (pintype "passive"))
      (node (ref "R12") (pin "2") (pinfunction "2_2") (pintype "passive"))
    )
    (net (code "50") (name "Net-(LED5-C)") (class "Default")
      (node (ref "LED5") (pin "2") (pinfunction "C_2") (pintype "passive"))
      (node (ref "R13") (pin "2") (pinfunction "2_2") (pintype "passive"))
    )
    (net (code "51") (name "Net-(LED6-C)") (class "Default")
      (node (ref "LED6") (pin "2") (pinfunction "C_2") (pintype "passive"))
      (node (ref "R14") (pin "2") (pinfunction "2_2") (pintype "passive"))
    )
    (net (code "52") (name "Net-(LED7-C)") (class "Default")
      (node (ref "LED7") (pin "2") (pinfunction "C_2") (pintype "passive"))
      (node (ref "R15") (pin "2") (pinfunction "2_2") (pintype "passive"))
    )
    (net (code "53") (name "Net-(LED8-C)") (class "Default")
      (node (ref "LED8") (pin "2") (pinfunction "C_2") (pintype "passive"))
      (node (ref "R46") (pin "2") (pinfunction "2_2") (pintype "passive"))
    )
    (net (code "54") (name "Net-(LED9-C)") (class "Default")
      (node (ref "LED9") (pin "2") (pinfunction "C_2") (pintype "passive"))
      (node (ref "R47") (pin "2") (pinfunction "2_2") (pintype "passive"))
    )
    (net (code "55") (name "Net-(LED10-BLUECATHODE)") (class "Default")
      (node (ref "LED10") (pin "3") (pinfunction "BLUECATHODE_3") (pintype "passive"))
      (node (ref "R4") (pin "2") (pinfunction "2_2") (pintype "passive"))
    )
    (net (code "56") (name "Net-(LED10-GREENCATHODE)") (class "Default")
      (node (ref "LED10") (pin "4") (pinfunction "GREENCATHODE_4") (pintype "passive"))
      (node (ref "R5") (pin "2") (pinfunction "2_2") (pintype "passive"))
    )
    (net (code "57") (name "Net-(LED10-REDCATHODE)") (class "Default")
      (node (ref "LED10") (pin "1") (pinfunction "REDCATHODE_1") (pintype "passive"))
      (node (ref "R3") (pin "2") (pinfunction "2_2") (pintype "passive"))
    )
    (net (code "58") (name "Net-(LED11-C)") (class "Default")
      (node (ref "LED11") (pin "1") (pinfunction "C_1") (pintype "passive"))
      (node (ref "R53") (pin "2") (pinfunction "2_2") (pintype "passive"))
    )
    (net (code "59") (name "Net-(LED12-C)") (class "Default")
      (node (ref "LED12") (pin "1") (pinfunction "C_1") (pintype "passive"))
      (node (ref "R54") (pin "2") (pinfunction "2_2") (pintype "passive"))
    )
    (net (code "60") (name "Net-(LED13-C)") (class "Default")
      (node (ref "LED13") (pin "2") (pinfunction "C_2") (pintype "passive"))
      (node (ref "R22") (pin "2") (pinfunction "2_2") (pintype "passive"))
    )
    (net (code "61") (name "Net-(LED14-C)") (class "Default")
      (node (ref "LED14") (pin "1") (pinfunction "C_1") (pintype "passive"))
      (node (ref "R55") (pin "2") (pinfunction "2_2") (pintype "passive"))
    )
    (net (code "62") (name "Net-(LED15-C)") (class "Default")
      (node (ref "LED15") (pin "1") (pinfunction "C_1") (pintype "passive"))
      (node (ref "R56") (pin "2") (pinfunction "2_2") (pintype "passive"))
    )
    (net (code "63") (name "Net-(M1--VM)") (class "Default")
      (node (ref "M1") (pin "P$2") (pinfunction "-VM_P$2") (pintype "bidirectional"))
      (node (ref "R57") (pin "2") (pinfunction "2_2") (pintype "passive"))
    )
    (net (code "64") (name "Net-(T1-E)") (class "Default")
      (node (ref "R26") (pin "2") (pinfunction "2_2") (pintype "passive"))
      (node (ref "T1") (pin "2") (pinfunction "E_2") (pintype "passive"))
      (node (ref "T3") (pin "1") (pinfunction "B_1") (pintype "passive"))
    )
    (net (code "65") (name "Net-(T11-B)") (class "Default")
      (node (ref "R43") (pin "2") (pinfunction "2_2") (pintype "passive"))
      (node (ref "T11") (pin "1") (pinfunction "B_1") (pintype "passive"))
      (node (ref "T2") (pin "2") (pinfunction "E_2") (pintype "passive"))
    )
    (net (code "66") (name "Net-(T13-B)") (class "Default")
      (node (ref "R17") (pin "2") (pinfunction "2_2") (pintype "passive"))
      (node (ref "T13") (pin "1") (pinfunction "B_1") (pintype "passive"))
      (node (ref "T4") (pin "2") (pinfunction "E_2") (pintype "passive"))
    )
    (net (code "67") (name "Net-(T14-B)") (class "Default")
      (node (ref "R18") (pin "2") (pinfunction "2_2") (pintype "passive"))
      (node (ref "T14") (pin "1") (pinfunction "B_1") (pintype "passive"))
      (node (ref "T5") (pin "2") (pinfunction "E_2") (pintype "passive"))
    )
    (net (code "68") (name "Net-(T15-B)") (class "Default")
      (node (ref "R19") (pin "2") (pinfunction "2_2") (pintype "passive"))
      (node (ref "T15") (pin "1") (pinfunction "B_1") (pintype "passive"))
      (node (ref "T6") (pin "2") (pinfunction "E_2") (pintype "passive"))
    )
    (net (code "69") (name "Net-(T16-B)") (class "Default")
      (node (ref "R20") (pin "2") (pinfunction "2_2") (pintype "passive"))
      (node (ref "T16") (pin "1") (pinfunction "B_1") (pintype "passive"))
      (node (ref "T7") (pin "2") (pinfunction "E_2") (pintype "passive"))
    )
    (net (code "70") (name "Net-(T17-B)") (class "Default")
      (node (ref "R21") (pin "2") (pinfunction "2_2") (pintype "passive"))
      (node (ref "T17") (pin "1") (pinfunction "B_1") (pintype "passive"))
      (node (ref "T8") (pin "2") (pinfunction "E_2") (pintype "passive"))
    )
    (net (code "71") (name "Net-(T18-B)") (class "Default")
      (node (ref "R24") (pin "2") (pinfunction "2_2") (pintype "passive"))
      (node (ref "T18") (pin "1") (pinfunction "B_1") (pintype "passive"))
      (node (ref "T9") (pin "2") (pinfunction "E_2") (pintype "passive"))
    )
    (net (code "72") (name "Net-(T19-G)") (class "Default")
      (node (ref "R28") (pin "2") (pinfunction "2_2") (pintype "passive"))
      (node (ref "T19") (pin "1") (pinfunction "G_1") (pintype "passive"))
    )
    (net (code "73") (name "Net-(T20-D)") (class "Default")
      (node (ref "R22") (pin "1") (pinfunction "1_1") (pintype "passive"))
      (node (ref "T20") (pin "3") (pinfunction "D_3") (pintype "passive"))
    )
    (net (code "74") (name "Net-(T20-G)") (class "Default")
      (node (ref "R23") (pin "2") (pinfunction "2_2") (pintype "passive"))
      (node (ref "T20") (pin "1") (pinfunction "G_1") (pintype "passive"))
    )
    (net (code "75") (name "Net-(T21-D)") (class "Default")
      (node (ref "R10") (pin "1") (pinfunction "1_1") (pintype "passive"))
      (node (ref "R11") (pin "1") (pinfunction "1_1") (pintype "passive"))
      (node (ref "R12") (pin "1") (pinfunction "1_1") (pintype "passive"))
      (node (ref "R13") (pin "1") (pinfunction "1_1") (pintype "passive"))
      (node (ref "R14") (pin "1") (pinfunction "1_1") (pintype "passive"))
      (node (ref "R15") (pin "1") (pinfunction "1_1") (pintype "passive"))
      (node (ref "R46") (pin "1") (pinfunction "1_1") (pintype "passive"))
      (node (ref "R47") (pin "1") (pinfunction "1_1") (pintype "passive"))
      (node (ref "T21") (pin "3") (pinfunction "D_3") (pintype "passive"))
    )
    (net (code "76") (name "Net-(T21-G)") (class "Default")
      (node (ref "R16") (pin "2") (pinfunction "2_2") (pintype "passive"))
      (node (ref "T21") (pin "1") (pinfunction "G_1") (pintype "passive"))
    )
    (net (code "77") (name "Net-(T22-G)") (class "Default")
      (node (ref "R2") (pin "2") (pinfunction "2_2") (pintype "passive"))
      (node (ref "T22") (pin "1") (pinfunction "G_1") (pintype "passive"))
    )
    (net (code "78") (name "Net-(T23-D)") (class "Default")
      (node (ref "R57") (pin "1") (pinfunction "1_1") (pintype "passive"))
      (node (ref "T23") (pin "3") (pinfunction "D_3") (pintype "passive"))
    )
    (net (code "79") (name "Net-(T23-G)") (class "Default")
      (node (ref "R58") (pin "2") (pinfunction "2_2") (pintype "passive"))
      (node (ref "T23") (pin "1") (pinfunction "G_1") (pintype "passive"))
    )
    (net (code "80") (name "Net-(U2-PROG)") (class "Default")
      (node (ref "R32") (pin "2") (pinfunction "2_2") (pintype "passive"))
      (node (ref "U2") (pin "6") (pinfunction "PROG_6") (pintype "bidirectional"))
    )
    (net (code "81") (name "Net-(U2-STAT1)") (class "Default")
      (node (ref "R1") (pin "1") (pinfunction "1_1") (pintype "passive"))
      (node (ref "U2") (pin "3") (pinfunction "STAT1_3") (pintype "bidirectional"))
    )
    (net (code "82") (name "Net-(U2-THERM)") (class "Default")
      (node (ref "R31") (pin "2") (pinfunction "2_2") (pintype "passive"))
      (node (ref "U2") (pin "8") (pinfunction "THERM_8") (pintype "bidirectional"))
    )
    (net (code "83") (name "Net-(U3-PD2(RXD1{slash}INT2))") (class "Default")
      (node (ref "CON5") (pin "2") (pinfunction "2_2") (pintype "bidirectional"))
      (node (ref "U3") (pin "P$27") (pinfunction "PD2(RXD1/INT2)_P$27") (pintype "bidirectional"))
    )
    (net (code "84") (name "Net-(U3-PD3(TXD1{slash}INT3))") (class "Default")
      (node (ref "CON5") (pin "1") (pinfunction "1_1") (pintype "bidirectional"))
      (node (ref "U3") (pin "P$28") (pinfunction "PD3(TXD1/INT3)_P$28") (pintype "bidirectional"))
    )
    (net (code "85") (name "Net-(U3-XTAL1)") (class "Default")
      (node (ref "C11") (pin "1") (pinfunction "1_1") (pintype "passive"))
      (node (ref "U3") (pin "P$24") (pinfunction "XTAL1_P$24") (pintype "bidirectional"))
      (node (ref "XTAL1") (pin "1") (pinfunction "1_1") (pintype "passive"))
    )
    (net (code "86") (name "Net-(U3-XTAL2)") (class "Default")
      (node (ref "C10") (pin "1") (pinfunction "1_1") (pintype "passive"))
      (node (ref "U3") (pin "P$23") (pinfunction "XTAL2_P$23") (pintype "bidirectional"))
      (node (ref "XTAL1") (pin "2") (pinfunction "2_2") (pintype "passive"))
    )
    (net (code "87") (name "Net-(U7-CT)") (class "Default")
      (node (ref "R51") (pin "1") (pinfunction "1_1") (pintype "passive"))
      (node (ref "U7") (pin "P$2") (pinfunction "CT_P$2") (pintype "bidirectional"))
    )
    (net (code "88") (name "Net-(U8-CT)") (class "Default")
      (node (ref "R50") (pin "1") (pinfunction "1_1") (pintype "passive"))
      (node (ref "U8") (pin "P$2") (pinfunction "CT_P$2") (pintype "bidirectional"))
    )
    (net (code "89") (name "PB0") (class "Default")
      (node (ref "R34") (pin "2") (pinfunction "2_2") (pintype "passive"))
      (node (ref "U3") (pin "P$10") (pinfunction "PB0(~{SS}/PCINT0)_P$10") (pintype "bidirectional"))
    )
    (net (code "90") (name "PB4") (class "Default")
      (node (ref "R60") (pin "2") (pinfunction "2_2") (pintype "passive"))
      (node (ref "U3") (pin "P$14") (pinfunction "PB4(OC2A/PCINT4)_P$14") (pintype "bidirectional"))
    )
    (net (code "91") (name "PB5") (class "Default")
      (node (ref "R59") (pin "2") (pinfunction "2_2") (pintype "passive"))
      (node (ref "U3") (pin "P$15") (pinfunction "PB5(OC1A/PCINT5)_P$15") (pintype "bidirectional"))
    )
    (net (code "92") (name "PB6") (class "Default")
      (node (ref "R52") (pin "2") (pinfunction "2_2") (pintype "passive"))
      (node (ref "U3") (pin "P$16") (pinfunction "PB6(OC1B/PCINT6)_P$16") (pintype "bidirectional"))
    )
    (net (code "93") (name "PB7") (class "Default")
      (node (ref "R62") (pin "2") (pinfunction "2_2") (pintype "passive"))
      (node (ref "U3") (pin "P$17") (pinfunction "PB7(OC0A/OC1C/PCINT7)_P$17") (pintype "bidirectional"))
    )
    (net (code "94") (name "RIGHTBUMPER") (class "Default")
      (node (ref "CON2") (pin "10") (pinfunction "10_10") (pintype "bidirectional"))
      (node (ref "U3") (pin "P$41") (pinfunction "PC6(A14)_P$41") (pintype "bidirectional"))
    )
    (net (code "95") (name "RX1") (class "Default")
      (node (ref "R36") (pin "1") (pinfunction "1_1") (pintype "passive"))
      (node (ref "R6") (pin "1") (pinfunction "1_1") (pintype "passive"))
      (node (ref "T13") (pin "3") (pinfunction "C_3") (pintype "passive"))
    )
    (net (code "96") (name "RX2") (class "Default")
      (node (ref "R25") (pin "1") (pinfunction "1_1") (pintype "passive"))
      (node (ref "R37") (pin "1") (pinfunction "1_1") (pintype "passive"))
      (node (ref "T14") (pin "3") (pinfunction "C_3") (pintype "passive"))
    )
    (net (code "97") (name "RX3") (class "Default")
      (node (ref "R34") (pin "1") (pinfunction "1_1") (pintype "passive"))
      (node (ref "R38") (pin "1") (pinfunction "1_1") (pintype "passive"))
      (node (ref "T15") (pin "3") (pinfunction "C_3") (pintype "passive"))
    )
    (net (code "98") (name "RX4") (class "Default")
      (node (ref "R39") (pin "1") (pinfunction "1_1") (pintype "passive"))
      (node (ref "R52") (pin "1") (pinfunction "1_1") (pintype "passive"))
      (node (ref "T16") (pin "3") (pinfunction "C_3") (pintype "passive"))
    )
    (net (code "99") (name "RX5") (class "Default")
      (node (ref "R40") (pin "1") (pinfunction "1_1") (pintype "passive"))
      (node (ref "R59") (pin "1") (pinfunction "1_1") (pintype "passive"))
      (node (ref "T17") (pin "3") (pinfunction "C_3") (pintype "passive"))
    )
    (net (code "100") (name "RX6") (class "Default")
      (node (ref "R41") (pin "1") (pinfunction "1_1") (pintype "passive"))
      (node (ref "R60") (pin "1") (pinfunction "1_1") (pintype "passive"))
      (node (ref "T18") (pin "3") (pinfunction "C_3") (pintype "passive"))
    )
    (net (code "101") (name "RX7") (class "Default")
      (node (ref "R44") (pin "1") (pinfunction "1_1") (pintype "passive"))
      (node (ref "R61") (pin "1") (pinfunction "1_1") (pintype "passive"))
      (node (ref "T3") (pin "3") (pinfunction "C_3") (pintype "passive"))
    )
    (net (code "102") (name "RX8") (class "Default")
      (node (ref "R45") (pin "1") (pinfunction "1_1") (pintype "passive"))
      (node (ref "R62") (pin "1") (pinfunction "1_1") (pintype "passive"))
      (node (ref "T11") (pin "3") (pinfunction "C_3") (pintype "passive"))
    )
    (net (code "103") (name "S+VSENSE") (class "Default")
      (node (ref "C14") (pin "1") (pinfunction "1_1") (pintype "passive"))
      (node (ref "CON7") (pin "1") (pinfunction "1_1") (pintype "bidirectional"))
      (node (ref "U7") (pin "P$1") (pinfunction "AN_P$1") (pintype "bidirectional"))
      (node (ref "U7") (pin "P$3") (pinfunction "C_P$3") (pintype "bidirectional"))
      (node (ref "U8") (pin "P$1") (pinfunction "AN_P$1") (pintype "bidirectional"))
      (node (ref "U8") (pin "P$3") (pinfunction "C_P$3") (pintype "bidirectional"))
      (node (ref "W3") (pin "P$1") (pinfunction "P$1_P$1") (pintype "bidirectional"))
      (node (ref "W3") (pin "P$2") (pinfunction "P$1_P$2") (pintype "bidirectional"))
    )
    (net (code "104") (name "SCK") (class "Default")
      (node (ref "CON1") (pin "5") (pinfunction "SCK_5") (pintype "bidirectional"))
      (node (ref "R25") (pin "2") (pinfunction "2_2") (pintype "passive"))
      (node (ref "U3") (pin "P$11") (pinfunction "PB1(SCK/PCINT1)_P$11") (pintype "bidirectional"))
    )
    (net (code "105") (name "SEN") (class "Default")
      (node (ref "T12") (pin "1") (pinfunction "G_1") (pintype "passive"))
      (node (ref "U3") (pin "P$4") (pinfunction "PE2(XCK0/AIN0)_P$4") (pintype "bidirectional"))
    )
    (net (code "106") (name "SGND") (class "Default")
      (node (ref "C14") (pin "2") (pinfunction "2_2") (pintype "passive"))
      (node (ref "CON7") (pin "8") (pinfunction "8_8") (pintype "bidirectional"))
      (node (ref "R33") (pin "1") (pinfunction "1_1") (pintype "passive"))
      (node (ref "R35") (pin "1") (pinfunction "1_1") (pintype "passive"))
      (node (ref "R48") (pin "1") (pinfunction "1_1") (pintype "passive"))
      (node (ref "R49") (pin "1") (pinfunction "1_1") (pintype "passive"))
      (node (ref "T22") (pin "2") (pinfunction "S_2") (pintype "passive"))
    )
    (net (code "107") (name "SIRENABLE") (class "Default")
      (node (ref "CON7") (pin "2") (pinfunction "2_2") (pintype "bidirectional"))
      (node (ref "R2") (pin "1") (pinfunction "1_1") (pintype "passive"))
    )
    (net (code "108") (name "SLEFTBUMPER") (class "Default")
      (node (ref "CON7") (pin "6") (pinfunction "6_6") (pintype "bidirectional"))
      (node (ref "R49") (pin "2") (pinfunction "2_2") (pintype "passive"))
      (node (ref "W1") (pin "P$1") (pinfunction "P$1_P$1") (pintype "bidirectional"))
      (node (ref "W1") (pin "P$2") (pinfunction "P$1_P$2") (pintype "bidirectional"))
    )
    (net (code "109") (name "SLINESENSE1") (class "Default")
      (node (ref "CON7") (pin "3") (pinfunction "3_3") (pintype "bidirectional"))
      (node (ref "R35") (pin "2") (pinfunction "2_2") (pintype "passive"))
      (node (ref "U8") (pin "P$4") (pinfunction "E_P$4") (pintype "bidirectional"))
    )
    (net (code "110") (name "SLINESENSE2") (class "Default")
      (node (ref "CON7") (pin "4") (pinfunction "4_4") (pintype "bidirectional"))
      (node (ref "R33") (pin "2") (pinfunction "2_2") (pintype "passive"))
      (node (ref "U7") (pin "P$4") (pinfunction "E_P$4") (pintype "bidirectional"))
    )
    (net (code "111") (name "SRIGHTBUMPER") (class "Default")
      (node (ref "CON7") (pin "7") (pinfunction "7_7") (pintype "bidirectional"))
      (node (ref "R48") (pin "2") (pinfunction "2_2") (pintype "passive"))
      (node (ref "W2") (pin "P$1") (pinfunction "P$1_P$1") (pintype "bidirectional"))
      (node (ref "W2") (pin "P$2") (pinfunction "P$1_P$2") (pintype "bidirectional"))
    )
    (net (code "112") (name "STBY") (class "Default")
      (node (ref "U$1") (pin "19") (pinfunction "STBY_19") (pintype "bidirectional"))
      (node (ref "U3") (pin "P$46") (pinfunction "PA5(AD5)_P$46") (pintype "bidirectional"))
    )
    (net (code "113") (name "TEMPSENSE") (class "Default")
      (node (ref "U3") (pin "P$54") (pinfunction "PF7(ADC7/TDI)_P$54") (pintype "bidirectional"))
      (node (ref "U4") (pin "2") (pinfunction "VOUT_2") (pintype "bidirectional"))
    )
    (net (code "114") (name "TRANSMITLEDS") (class "Default")
      (node (ref "R16") (pin "1") (pinfunction "1_1") (pintype "passive"))
      (node (ref "U3") (pin "P$29") (pinfunction "PD4(ICP1)_P$29") (pintype "bidirectional"))
    )
    (net (code "115") (name "VBATSENSE") (class "Default")
      (node (ref "C15") (pin "1") (pinfunction "1_1") (pintype "passive"))
      (node (ref "R29") (pin "1") (pinfunction "1_1") (pintype "passive"))
      (node (ref "R30") (pin "2") (pinfunction "2_2") (pintype "passive"))
      (node (ref "U3") (pin "P$61") (pinfunction "PF0(ADC0)_P$61") (pintype "bidirectional"))
    )
    (net (code "116") (name "VIBE") (class "Default")
      (node (ref "R58") (pin "1") (pinfunction "1_1") (pintype "passive"))
      (node (ref "U3") (pin "P$36") (pinfunction "PC1(A9)_P$36") (pintype "bidirectional"))
    )
    (net (code "117") (name "unconnected-(CON2-Pad12)") (class "Default")
      (node (ref "CON2") (pin "12") (pinfunction "12_12") (pintype "bidirectional"))
    )
    (net (code "118") (name "unconnected-(CON7-Pad5)") (class "Default")
      (node (ref "CON7") (pin "5") (pinfunction "5_5") (pintype "bidirectional"))
    )
    (net (code "119") (name "unconnected-(SW1-Pad1)") (class "Default")
      (node (ref "SW1") (pin "1") (pinfunction "1_1") (pintype "bidirectional"))
    )
    (net (code "120") (name "unconnected-(SW1-Pad4)") (class "Default")
      (node (ref "SW1") (pin "4") (pinfunction "4_4") (pintype "bidirectional"))
    )
    (net (code "121") (name "unconnected-(U3-PA0(AD0)-PadP$51)") (class "Default")
      (node (ref "U3") (pin "P$51") (pinfunction "PA0(AD0)_P$51") (pintype "bidirectional"))
    )
    (net (code "122") (name "unconnected-(U3-PD5(XCK1)-PadP$30)") (class "Default")
      (node (ref "U3") (pin "P$30") (pinfunction "PD5(XCK1)_P$30") (pintype "bidirectional"))
    )
    (net (code "123") (name "unconnected-(U3-PD6(T1)-PadP$31)") (class "Default")
      (node (ref "U3") (pin "P$31") (pinfunction "PD6(T1)_P$31") (pintype "bidirectional"))
    )
    (net (code "124") (name "unconnected-(U3-PD7(T0)-PadP$32)") (class "Default")
      (node (ref "U3") (pin "P$32") (pinfunction "PD7(T0)_P$32") (pintype "bidirectional"))
    )
    (net (code "125") (name "unconnected-(U3-PE6(T3{slash}INT6)-PadP$8)") (class "Default")
      (node (ref "U3") (pin "P$8") (pinfunction "PE6(T3/INT6)_P$8") (pintype "bidirectional"))
    )
    (net (code "126") (name "unconnected-(U3-PE7(ICP3{slash}CLKO{slash}INT7)-PadP$9)") (class "Default")
      (node (ref "U3") (pin "P$9") (pinfunction "PE7(ICP3/CLKO/INT7)_P$9") (pintype "bidirectional"))
    )
    (net (code "127") (name "unconnected-(U3-PG3(TOSC2)-PadP$18)") (class "Default")
      (node (ref "U3") (pin "P$18") (pinfunction "PG3(TOSC2)_P$18") (pintype "bidirectional"))
    )
    (net (code "128") (name "unconnected-(U3-PG4(TOSC1)-PadP$19)") (class "Default")
      (node (ref "U3") (pin "P$19") (pinfunction "PG4(TOSC1)_P$19") (pintype "bidirectional"))
    )
  )
)
